# LAN8670_Watson.net
KiCad netlist of a schematic drawn in Altium Designer
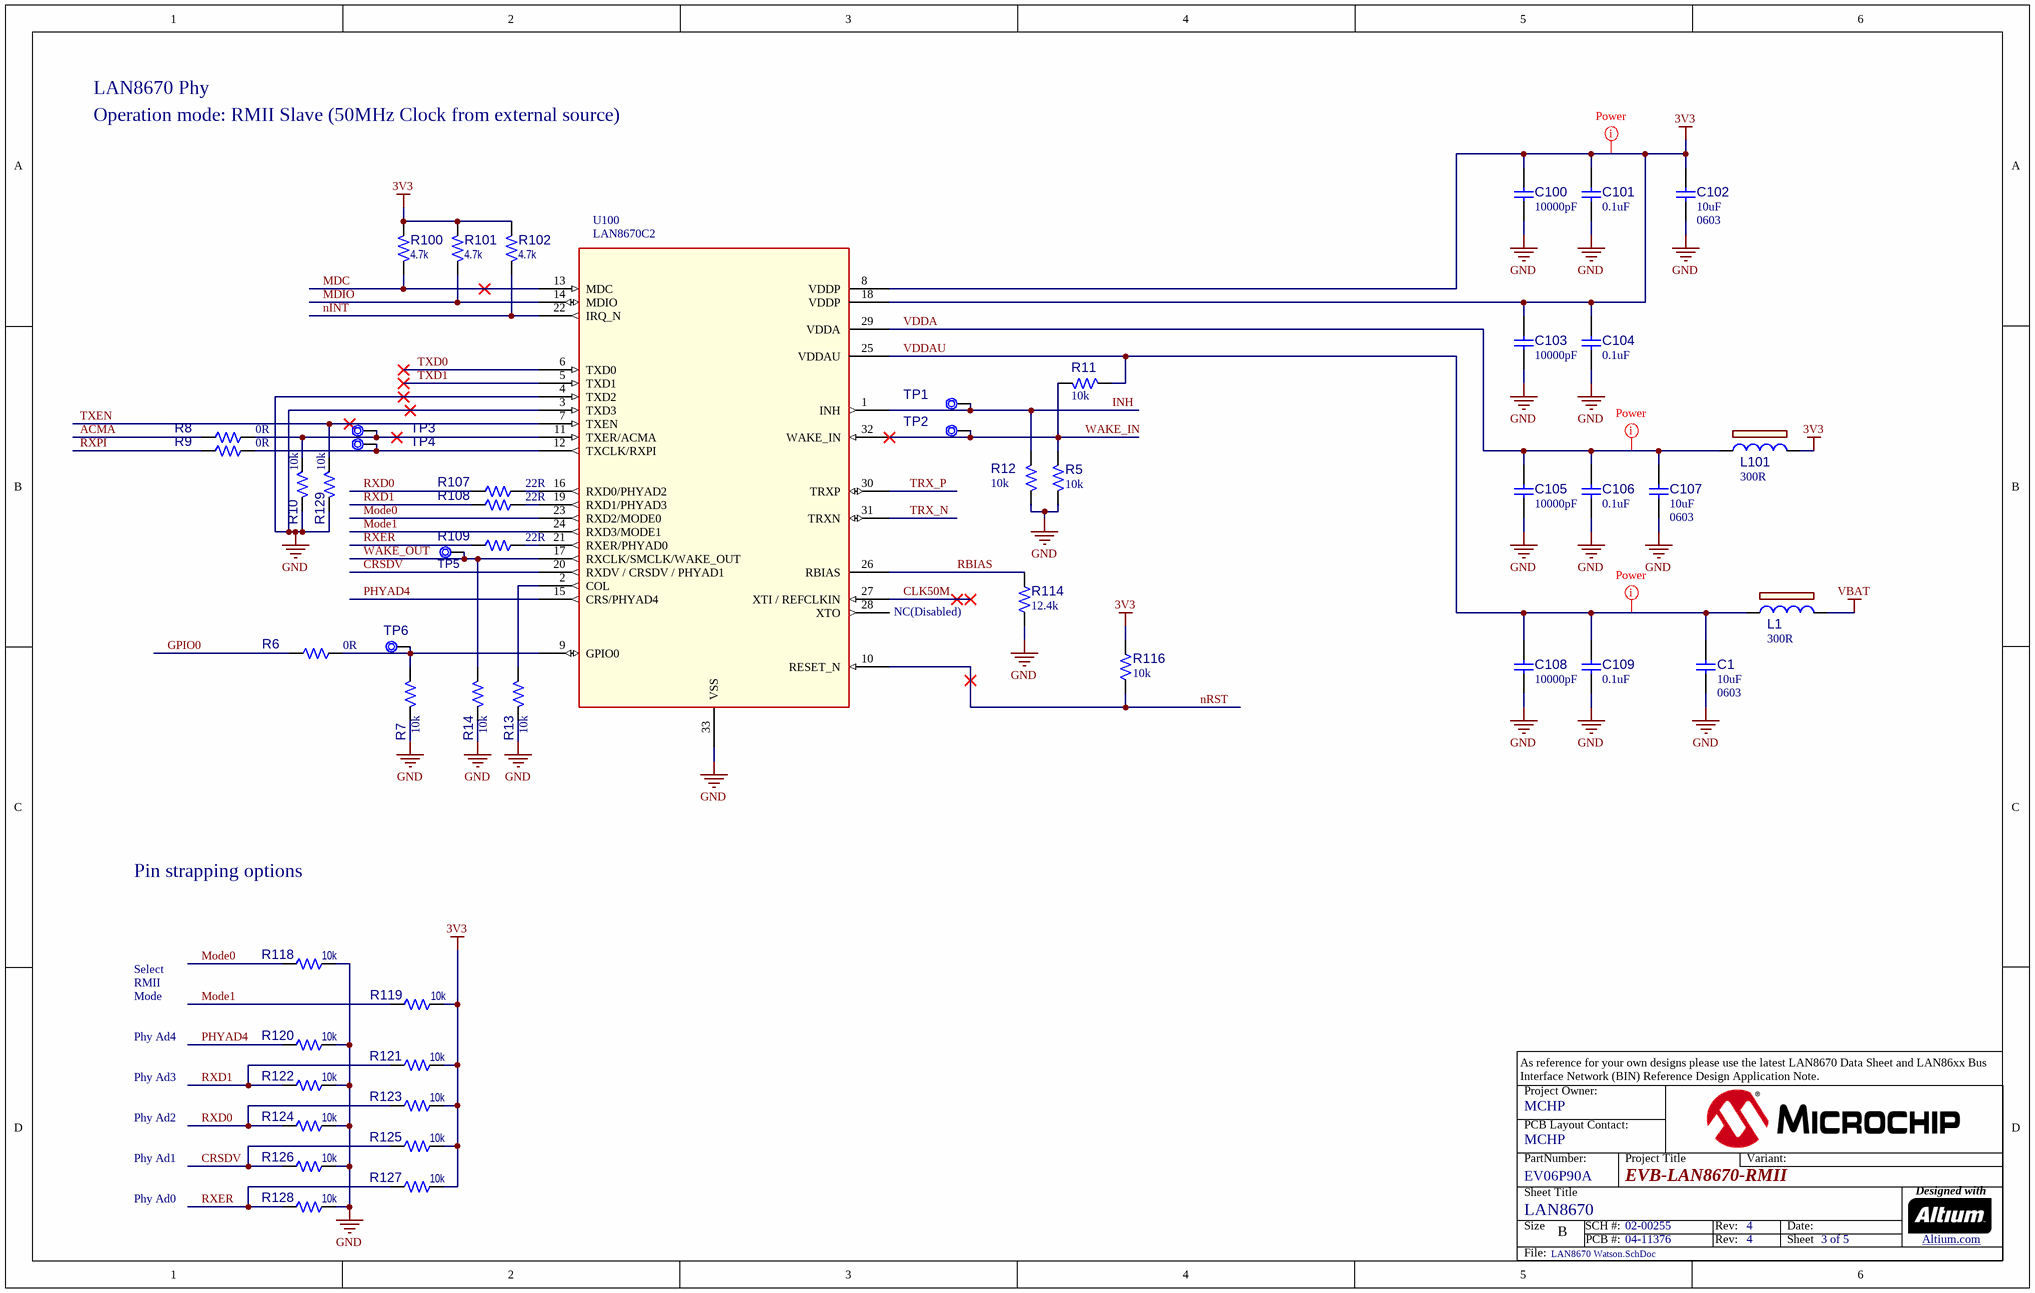
[diagram p0: LAN8670 Watson.SchDoc]

(export (version "E")
  (design (tool "Eeschema 10.0.6"))
  (components
    (comp (ref "C1")
      (value "10uF")
      (footprint "CAP_C_0603")
      (fields
        (field (name "VOLTAGE") "10V")
        (field (name "PACKAGE") "0603")
        (field (name "TOLERANCE") "20%")
        (field (name "Comment") "Capacitor NP")
      )
      (libsource (lib "") (part "Capacitor NP_1"))
    )
    (comp (ref "C100")
      (value "10000pF")
      (footprint "CAP_C_0402")
      (fields
        (field (name "VOLTAGE") "50V")
        (field (name "TOLERANCE") "10%")
        (field (name "Comment") "Capacitor NP")
        (field (name "OWNER") "Gabor Bihari")
      )
      (libsource (lib "MCHP-CDB-Offline") (part "Capacitor NP"))
    )
    (comp (ref "C101")
      (value "0.1uF")
      (footprint "CAP_C_0402")
      (description "Capacitor")
      (fields
        (field (name "VOLTAGE") "16V")
        (field (name "TOLERANCE") "10%")
        (field (name "OWNER") "Sompoch Loboonlert")
      )
      (libsource (lib "MCHP-CDB") (part "Capacitor NP"))
    )
    (comp (ref "C102")
      (value "10uF")
      (footprint "CAP_C_0603")
      (description "Capacitor")
      (fields (field (name "VOLTAGE") "10V") (field (name "PACKAGE") "0603") (field (name "TOLERANCE") "20%"))
      (libsource (lib "MCHP-CDB") (part "Capacitor NP"))
    )
    (comp (ref "C103")
      (value "10000pF")
      (footprint "CAP_C_0402")
      (fields
        (field (name "VOLTAGE") "50V")
        (field (name "TOLERANCE") "10%")
        (field (name "Comment") "Capacitor NP")
        (field (name "OWNER") "Gabor Bihari")
      )
      (libsource (lib "MCHP-CDB-Offline") (part "Capacitor NP"))
    )
    (comp (ref "C104")
      (value "0.1uF")
      (footprint "CAP_C_0402")
      (description "Capacitor")
      (fields
        (field (name "VOLTAGE") "16V")
        (field (name "TOLERANCE") "10%")
        (field (name "OWNER") "Sompoch Loboonlert")
      )
      (libsource (lib "MCHP-CDB") (part "Capacitor NP"))
    )
    (comp (ref "C105")
      (value "10000pF")
      (footprint "CAP_C_0402")
      (fields
        (field (name "VOLTAGE") "50V")
        (field (name "TOLERANCE") "10%")
        (field (name "Comment") "Capacitor NP")
        (field (name "OWNER") "Gabor Bihari")
      )
      (libsource (lib "MCHP-CDB-Offline") (part "Capacitor NP"))
    )
    (comp (ref "C106")
      (value "0.1uF")
      (footprint "CAP_C_0402")
      (description "Capacitor")
      (fields
        (field (name "VOLTAGE") "16V")
        (field (name "TOLERANCE") "10%")
        (field (name "OWNER") "Sompoch Loboonlert")
      )
      (libsource (lib "MCHP-CDB") (part "Capacitor NP"))
    )
    (comp (ref "C107")
      (value "10uF")
      (footprint "CAP_C_0603")
      (description "Capacitor")
      (fields (field (name "VOLTAGE") "10V") (field (name "PACKAGE") "0603") (field (name "TOLERANCE") "20%"))
      (libsource (lib "MCHP-CDB") (part "Capacitor NP"))
    )
    (comp (ref "C108")
      (value "10000pF")
      (footprint "CAP_C_0402")
      (fields
        (field (name "VOLTAGE") "50V")
        (field (name "TOLERANCE") "10%")
        (field (name "Comment") "Capacitor NP")
        (field (name "OWNER") "Gabor Bihari")
      )
      (libsource (lib "MCHP-CDB-Offline") (part "Capacitor NP"))
    )
    (comp (ref "C109")
      (value "0.1uF")
      (footprint "CAP_C_0402")
      (description "Capacitor")
      (fields
        (field (name "VOLTAGE") "16V")
        (field (name "TOLERANCE") "10%")
        (field (name "OWNER") "Sompoch Loboonlert")
      )
      (libsource (lib "MCHP-CDB") (part "Capacitor NP"))
    )
    (comp (ref "L1")
      (value "300R")
      (footprint "IND_C_0603")
      (fields (field (name "Comment") "Ferrite Bead") (field (name "OWNER") "Lori Graham"))
      (libsource (lib "MCHP-CDB") (part "Ferrite Bead"))
    )
    (comp (ref "L101")
      (value "300R")
      (footprint "IND_C_0603")
      (fields (field (name "Comment") "Ferrite Bead") (field (name "OWNER") "Lori Graham"))
      (libsource (lib "MCL-Offline") (part "Ferrite Bead"))
    )
    (comp (ref "R5")
      (value "10k")
      (footprint "RES_C_0402")
      (description "Resistor")
      (fields
        (field (name "VOLTAGE") "50V")
        (field (name "POWER") "1/10W")
        (field (name "OWNER") "Brent Lanphear")
      )
      (libsource (lib "") (part "Resistor_1"))
    )
    (comp (ref "R6")
      (value "0R")
      (footprint "RES_C_0402")
      (description "Resistor")
      (fields
        (field (name "TOLERANCE") "50mOhm")
        (field (name "POWER") "1/10W")
        (field (name "OWNER") "Dragos Danaila")
      )
      (libsource (lib "MCL-Offline") (part "Resistor"))
    )
    (comp (ref "R7")
      (value "10k")
      (footprint "RES_C_0402")
      (description "Resistor")
      (fields
        (field (name "TOLERANCE") "1%")
        (field (name "VOLTAGE") "50V")
        (field (name "OWNER") "Brent Lanphear")
      )
      (libsource (lib "MCHP-CDB") (part "Resistor"))
    )
    (comp (ref "R8")
      (value "0R")
      (footprint "RES_C_0402")
      (description "Resistor")
      (fields
        (field (name "TOLERANCE") "50mOhm")
        (field (name "POWER") "1/10W")
        (field (name "OWNER") "Dragos Danaila")
      )
      (libsource (lib "MCL-Offline") (part "Resistor"))
    )
    (comp (ref "R9")
      (value "0R")
      (footprint "RES_C_0402")
      (description "Resistor")
      (fields
        (field (name "TOLERANCE") "50mOhm")
        (field (name "POWER") "1/10W")
        (field (name "OWNER") "Dragos Danaila")
      )
      (libsource (lib "MCL-Offline") (part "Resistor"))
    )
    (comp (ref "R10")
      (value "10k")
      (footprint "RES_C_0402")
      (description "Resistor")
      (fields
        (field (name "TOLERANCE") "1%")
        (field (name "VOLTAGE") "50V")
        (field (name "OWNER") "Brent Lanphear")
      )
      (libsource (lib "MCHP-CDB") (part "Resistor"))
    )
    (comp (ref "R11")
      (value "10k")
      (footprint "RES_C_0402")
      (description "Resistor")
      (fields
        (field (name "TOLERANCE") "1%")
        (field (name "VOLTAGE") "50V")
        (field (name "OWNER") "Brent Lanphear")
      )
      (libsource (lib "MCHP-CDB") (part "Resistor"))
    )
    (comp (ref "R12")
      (value "10k")
      (footprint "RES_C_0402")
      (description "Resistor")
      (fields
        (field (name "TOLERANCE") "1%")
        (field (name "VOLTAGE") "50V")
        (field (name "OWNER") "Brent Lanphear")
      )
      (libsource (lib "MCHP-CDB") (part "Resistor"))
    )
    (comp (ref "R13")
      (value "10k")
      (footprint "RES_C_0402")
      (description "Resistor")
      (fields
        (field (name "TOLERANCE") "1%")
        (field (name "VOLTAGE") "50V")
        (field (name "OWNER") "Brent Lanphear")
      )
      (libsource (lib "MCHP-CDB") (part "Resistor"))
    )
    (comp (ref "R14")
      (value "10k")
      (footprint "RES_C_0402")
      (description "Resistor")
      (fields
        (field (name "TOLERANCE") "1%")
        (field (name "VOLTAGE") "50V")
        (field (name "OWNER") "Brent Lanphear")
      )
      (libsource (lib "MCHP-CDB") (part "Resistor"))
    )
    (comp (ref "R100")
      (value "4.7k")
      (footprint "RES_C_0402")
      (description "Resistor")
      (fields
        (field (name "VOLTAGE") "50V")
        (field (name "POWER") "1/10W")
        (field (name "OWNER") "Stephen Humberd")
      )
      (libsource (lib "MCHP-CDB") (part "Resistor"))
    )
    (comp (ref "R101")
      (value "4.7k")
      (footprint "RES_C_0402")
      (description "Resistor")
      (fields
        (field (name "VOLTAGE") "50V")
        (field (name "POWER") "1/10W")
        (field (name "OWNER") "Stephen Humberd")
      )
      (libsource (lib "MCHP-CDB") (part "Resistor"))
    )
    (comp (ref "R102")
      (value "4.7k")
      (footprint "RES_C_0402")
      (description "Resistor")
      (fields
        (field (name "VOLTAGE") "50V")
        (field (name "POWER") "1/10W")
        (field (name "OWNER") "Stephen Humberd")
      )
      (libsource (lib "MCHP-CDB") (part "Resistor"))
    )
    (comp (ref "R107")
      (value "22R")
      (footprint "RES_C_0402")
      (description "Resistor")
      (fields
        (field (name "TOLERANCE") "1%")
        (field (name "POWER") "1/10W")
        (field (name "OWNER") "Mike Ragsdale")
      )
      (libsource (lib "MCHP-CDB-Offline") (part "Resistor"))
    )
    (comp (ref "R108")
      (value "22R")
      (footprint "RES_C_0402")
      (description "Resistor")
      (fields
        (field (name "TOLERANCE") "1%")
        (field (name "POWER") "1/10W")
        (field (name "OWNER") "Mike Ragsdale")
      )
      (libsource (lib "MCHP-CDB-Offline") (part "Resistor"))
    )
    (comp (ref "R109")
      (value "22R")
      (footprint "RES_C_0402")
      (description "Resistor")
      (fields
        (field (name "TOLERANCE") "1%")
        (field (name "POWER") "1/10W")
        (field (name "OWNER") "Mike Ragsdale")
      )
      (libsource (lib "MCHP-CDB-Offline") (part "Resistor"))
    )
    (comp (ref "R114")
      (value "12.4k")
      (footprint "RES_C_0402")
      (description "Resistor")
      (fields
        (field (name "TOLERANCE") "±1%")
        (field (name "POWER") "1/10W")
        (field (name "OWNER") "Lori Graham")
      )
      (libsource (lib "MCL-Offline") (part "Resistor"))
    )
    (comp (ref "R116")
      (value "10k")
      (footprint "RES_C_0402")
      (description "Resistor")
      (fields
        (field (name "TOLERANCE") "1%")
        (field (name "VOLTAGE") "50V")
        (field (name "OWNER") "Brent Lanphear")
      )
      (libsource (lib "") (part "Resistor_1"))
    )
    (comp (ref "R118")
      (value "10k")
      (footprint "RES_C_0402")
      (description "Resistor")
      (fields
        (field (name "TOLERANCE") "1%")
        (field (name "VOLTAGE") "50V")
        (field (name "OWNER") "Brent Lanphear")
      )
      (libsource (lib "MCHP-CDB") (part "Resistor"))
    )
    (comp (ref "R119")
      (value "10k")
      (footprint "RES_C_0402")
      (description "Resistor")
      (fields
        (field (name "TOLERANCE") "1%")
        (field (name "VOLTAGE") "50V")
        (field (name "OWNER") "Brent Lanphear")
      )
      (libsource (lib "MCHP-CDB") (part "Resistor"))
    )
    (comp (ref "R120")
      (value "10k")
      (footprint "RES_C_0402")
      (description "Resistor")
      (fields
        (field (name "TOLERANCE") "1%")
        (field (name "VOLTAGE") "50V")
        (field (name "OWNER") "Brent Lanphear")
      )
      (libsource (lib "MCHP-CDB") (part "Resistor"))
    )
    (comp (ref "R121")
      (value "10k")
      (footprint "RES_C_0402")
      (description "Resistor")
      (fields
        (field (name "TOLERANCE") "1%")
        (field (name "VOLTAGE") "50V")
        (field (name "OWNER") "Brent Lanphear")
      )
      (libsource (lib "MCHP-CDB") (part "Resistor"))
    )
    (comp (ref "R122")
      (value "10k")
      (footprint "RES_C_0402")
      (description "Resistor")
      (fields
        (field (name "TOLERANCE") "1%")
        (field (name "VOLTAGE") "50V")
        (field (name "OWNER") "Brent Lanphear")
      )
      (libsource (lib "MCHP-CDB") (part "Resistor"))
    )
    (comp (ref "R123")
      (value "10k")
      (footprint "RES_C_0402")
      (description "Resistor")
      (fields
        (field (name "TOLERANCE") "1%")
        (field (name "VOLTAGE") "50V")
        (field (name "OWNER") "Brent Lanphear")
      )
      (libsource (lib "MCHP-CDB") (part "Resistor"))
    )
    (comp (ref "R124")
      (value "10k")
      (footprint "RES_C_0402")
      (description "Resistor")
      (fields
        (field (name "TOLERANCE") "1%")
        (field (name "VOLTAGE") "50V")
        (field (name "OWNER") "Brent Lanphear")
      )
      (libsource (lib "MCHP-CDB") (part "Resistor"))
    )
    (comp (ref "R125")
      (value "10k")
      (footprint "RES_C_0402")
      (description "Resistor")
      (fields
        (field (name "TOLERANCE") "1%")
        (field (name "VOLTAGE") "50V")
        (field (name "OWNER") "Brent Lanphear")
      )
      (libsource (lib "MCHP-CDB") (part "Resistor"))
    )
    (comp (ref "R126")
      (value "10k")
      (footprint "RES_C_0402")
      (description "Resistor")
      (fields
        (field (name "TOLERANCE") "1%")
        (field (name "VOLTAGE") "50V")
        (field (name "OWNER") "Brent Lanphear")
      )
      (libsource (lib "MCHP-CDB") (part "Resistor"))
    )
    (comp (ref "R127")
      (value "10k")
      (footprint "RES_C_0402")
      (description "Resistor")
      (fields
        (field (name "TOLERANCE") "1%")
        (field (name "VOLTAGE") "50V")
        (field (name "OWNER") "Brent Lanphear")
      )
      (libsource (lib "MCHP-CDB") (part "Resistor"))
    )
    (comp (ref "R128")
      (value "10k")
      (footprint "RES_C_0402")
      (description "Resistor")
      (fields
        (field (name "TOLERANCE") "1%")
        (field (name "VOLTAGE") "50V")
        (field (name "OWNER") "Brent Lanphear")
      )
      (libsource (lib "MCHP-CDB") (part "Resistor"))
    )
    (comp (ref "R129")
      (value "10k")
      (footprint "RES_C_0402")
      (description "Resistor")
      (fields
        (field (name "TOLERANCE") "1%")
        (field (name "VOLTAGE") "50V")
        (field (name "OWNER") "Brent Lanphear")
      )
      (libsource (lib "MCHP-CDB") (part "Resistor"))
    )
    (comp (ref "TP1")
      (value "Test Point No BOM")
      (footprint "TP_rd_0.5mm")
      (description "Test Point")
      (fields (field (name "OWNER") "JBU  (M21065)"))
      (libsource (lib "AIS-CDB-Offline") (part "Test Point No BOM"))
    )
    (comp (ref "TP2")
      (value "Test Point No BOM")
      (footprint "TP_rd_0.5mm")
      (description "Test Point")
      (fields (field (name "OWNER") "JBU  (M21065)"))
      (libsource (lib "AIS-CDB-Offline") (part "Test Point No BOM"))
    )
    (comp (ref "TP3")
      (value "Test Point No BOM")
      (footprint "TP_rd_0.5mm")
      (description "Test Point")
      (fields (field (name "OWNER") "JBU  (M21065)"))
      (libsource (lib "AIS-CDB-Offline") (part "Test Point No BOM"))
    )
    (comp (ref "TP4")
      (value "Test Point No BOM")
      (footprint "TP_rd_0.5mm")
      (description "Test Point")
      (fields (field (name "OWNER") "JBU  (M21065)"))
      (libsource (lib "AIS-CDB-Offline") (part "Test Point No BOM"))
    )
    (comp (ref "TP5")
      (value "Test Point No BOM")
      (footprint "TP_rd_0.5mm")
      (description "Test Point")
      (fields (field (name "OWNER") "JBU  (M21065)"))
      (libsource (lib "AIS-CDB-Offline") (part "Test Point No BOM"))
    )
    (comp (ref "TP6")
      (value "Test Point No BOM")
      (footprint "TP_rd_0.5mm")
      (description "Test Point")
      (fields (field (name "OWNER") "JBU  (M21065)"))
      (libsource (lib "AIS-CDB-Offline") (part "Test Point No BOM"))
    )
    (comp (ref "U100")
      (value "LAN8670C2")
      (footprint "VQFN-32_5x5_EP3.3x3.3")
      (fields (field (name "Comment") "LAN8670C VQFN-32") (field (name "OWNER") "Lori Cantrell"))
      (libsource (lib "MCL-Offline") (part "LAN8670C VQFN-32"))
    )
  )
  (nets
    (net (code "1") (name "/ACMA") (class "Default")
      (node (ref "R8") (pin "1") (pinfunction "1_1") (pintype "passive"))
    )
    (net (code "2") (name "/CLK50M") (class "Default")
      (node (ref "U100") (pin "27") (pinfunction "XTI_/_REFCLKIN_27") (pintype "input+no_connect"))
    )
    (net (code "3") (name "/CRSDV") (class "Default")
      (node (ref "R125") (pin "1") (pinfunction "1_1") (pintype "passive"))
      (node (ref "R126") (pin "1") (pinfunction "1_1") (pintype "passive"))
      (node (ref "U100") (pin "20") (pinfunction "RXDV_/_CRSDV_/_PHYAD1_20") (pintype "output"))
    )
    (net (code "4") (name "/GPIO0") (class "Default")
      (node (ref "R6") (pin "1") (pinfunction "1_1") (pintype "passive"))
    )
    (net (code "5") (name "/INH") (class "Default")
      (node (ref "R12") (pin "2") (pinfunction "2_2") (pintype "passive"))
      (node (ref "TP1") (pin "1") (pinfunction "1_1") (pintype "passive"))
      (node (ref "U100") (pin "1") (pinfunction "INH_1") (pintype "output"))
    )
    (net (code "6") (name "/MDC") (class "Default")
      (node (ref "R100") (pin "1") (pinfunction "1_1") (pintype "passive"))
      (node (ref "U100") (pin "13") (pinfunction "MDC_13") (pintype "input"))
    )
    (net (code "7") (name "/MDIO") (class "Default")
      (node (ref "R101") (pin "1") (pinfunction "1_1") (pintype "passive"))
      (node (ref "U100") (pin "14") (pinfunction "MDIO_14") (pintype "bidirectional"))
    )
    (net (code "8") (name "/Mode0") (class "Default")
      (node (ref "R118") (pin "1") (pinfunction "1_1") (pintype "passive"))
      (node (ref "U100") (pin "23") (pinfunction "RXD2/MODE0_23") (pintype "output"))
    )
    (net (code "9") (name "/Mode1") (class "Default")
      (node (ref "R119") (pin "1") (pinfunction "1_1") (pintype "passive"))
      (node (ref "U100") (pin "24") (pinfunction "RXD3/MODE1_24") (pintype "output"))
    )
    (net (code "10") (name "/PHYAD4") (class "Default")
      (node (ref "R120") (pin "1") (pinfunction "1_1") (pintype "passive"))
      (node (ref "U100") (pin "15") (pinfunction "CRS/PHYAD4_15") (pintype "output"))
    )
    (net (code "11") (name "/RBIAS") (class "Default")
      (node (ref "R114") (pin "2") (pinfunction "2_2") (pintype "passive"))
      (node (ref "U100") (pin "26") (pinfunction "RBIAS_26") (pintype "passive"))
    )
    (net (code "12") (name "/RXD0") (class "Default")
      (node (ref "R107") (pin "1") (pinfunction "1_1") (pintype "passive"))
      (node (ref "R123") (pin "1") (pinfunction "1_1") (pintype "passive"))
      (node (ref "R124") (pin "1") (pinfunction "1_1") (pintype "passive"))
    )
    (net (code "13") (name "/RXD1") (class "Default")
      (node (ref "R108") (pin "1") (pinfunction "1_1") (pintype "passive"))
      (node (ref "R121") (pin "1") (pinfunction "1_1") (pintype "passive"))
      (node (ref "R122") (pin "1") (pinfunction "1_1") (pintype "passive"))
    )
    (net (code "14") (name "/RXER") (class "Default")
      (node (ref "R109") (pin "1") (pinfunction "1_1") (pintype "passive"))
      (node (ref "R127") (pin "1") (pinfunction "1_1") (pintype "passive"))
      (node (ref "R128") (pin "1") (pinfunction "1_1") (pintype "passive"))
    )
    (net (code "15") (name "/RXPI") (class "Default")
      (node (ref "R9") (pin "1") (pinfunction "1_1") (pintype "passive"))
    )
    (net (code "16") (name "/TRX_N") (class "Default")
      (node (ref "U100") (pin "31") (pinfunction "TRXN_31") (pintype "bidirectional"))
    )
    (net (code "17") (name "/TRX_P") (class "Default")
      (node (ref "U100") (pin "30") (pinfunction "TRXP_30") (pintype "bidirectional"))
    )
    (net (code "18") (name "/TXD0") (class "Default")
      (node (ref "U100") (pin "6") (pinfunction "TXD0_6") (pintype "input+no_connect"))
    )
    (net (code "19") (name "/TXD1") (class "Default")
      (node (ref "U100") (pin "5") (pinfunction "TXD1_5") (pintype "input+no_connect"))
    )
    (net (code "20") (name "/TXEN") (class "Default")
      (node (ref "R129") (pin "2") (pinfunction "2_2") (pintype "passive"))
      (node (ref "U100") (pin "7") (pinfunction "TXEN_7") (pintype "input"))
    )
    (net (code "21") (name "/VDDA") (class "Default")
      (node (ref "C105") (pin "2") (pinfunction "2_2") (pintype "passive"))
      (node (ref "C106") (pin "2") (pinfunction "2_2") (pintype "passive"))
      (node (ref "C107") (pin "2") (pinfunction "2_2") (pintype "passive"))
      (node (ref "L101") (pin "1") (pinfunction "1_1") (pintype "passive"))
      (node (ref "U100") (pin "29") (pinfunction "VDDA_29") (pintype "power_in"))
    )
    (net (code "22") (name "/VDDAU") (class "Default")
      (node (ref "C1") (pin "2") (pinfunction "2_2") (pintype "passive"))
      (node (ref "C108") (pin "2") (pinfunction "2_2") (pintype "passive"))
      (node (ref "C109") (pin "2") (pinfunction "2_2") (pintype "passive"))
      (node (ref "L1") (pin "1") (pinfunction "1_1") (pintype "passive"))
      (node (ref "R11") (pin "1") (pinfunction "1_1") (pintype "passive"))
      (node (ref "U100") (pin "25") (pinfunction "VDDAU_25") (pintype "power_in"))
    )
    (net (code "23") (name "/WAKE_IN") (class "Default")
      (node (ref "R11") (pin "2") (pinfunction "2_2") (pintype "passive"))
      (node (ref "R5") (pin "2") (pinfunction "2_2") (pintype "passive"))
      (node (ref "TP2") (pin "1") (pinfunction "1_1") (pintype "passive"))
      (node (ref "U100") (pin "32") (pinfunction "WAKE_IN_32") (pintype "input"))
    )
    (net (code "24") (name "/WAKE_OUT") (class "Default")
      (node (ref "R14") (pin "2") (pinfunction "2_2") (pintype "passive"))
      (node (ref "TP5") (pin "1") (pinfunction "1_1") (pintype "passive"))
      (node (ref "U100") (pin "17") (pinfunction "RXCLK/SMCLK/WAKE_OUT_17") (pintype "output"))
    )
    (net (code "25") (name "/nINT") (class "Default")
      (node (ref "R102") (pin "1") (pinfunction "1_1") (pintype "passive"))
      (node (ref "U100") (pin "22") (pinfunction "IRQ_N_22") (pintype "output"))
    )
    (net (code "26") (name "/nRST") (class "Default")
      (node (ref "R116") (pin "1") (pinfunction "1_1") (pintype "passive"))
      (node (ref "U100") (pin "10") (pinfunction "RESET_N_10") (pintype "input"))
    )
    (net (code "27") (name "3V3") (class "Default")
      (node (ref "C100") (pin "2") (pinfunction "2_2") (pintype "passive"))
      (node (ref "C101") (pin "2") (pinfunction "2_2") (pintype "passive"))
      (node (ref "C102") (pin "2") (pinfunction "2_2") (pintype "passive"))
      (node (ref "C103") (pin "2") (pinfunction "2_2") (pintype "passive"))
      (node (ref "C104") (pin "2") (pinfunction "2_2") (pintype "passive"))
      (node (ref "L101") (pin "2") (pinfunction "2_2") (pintype "passive"))
      (node (ref "R100") (pin "2") (pinfunction "2_2") (pintype "passive"))
      (node (ref "R101") (pin "2") (pinfunction "2_2") (pintype "passive"))
      (node (ref "R102") (pin "2") (pinfunction "2_2") (pintype "passive"))
      (node (ref "R116") (pin "2") (pinfunction "2_2") (pintype "passive"))
      (node (ref "R119") (pin "2") (pinfunction "2_2") (pintype "passive"))
      (node (ref "R121") (pin "2") (pinfunction "2_2") (pintype "passive"))
      (node (ref "R123") (pin "2") (pinfunction "2_2") (pintype "passive"))
      (node (ref "R125") (pin "2") (pinfunction "2_2") (pintype "passive"))
      (node (ref "R127") (pin "2") (pinfunction "2_2") (pintype "passive"))
      (node (ref "U100") (pin "18") (pinfunction "VDDP_18") (pintype "power_in"))
      (node (ref "U100") (pin "8") (pinfunction "VDDP_8") (pintype "power_in"))
    )
    (net (code "28") (name "GND") (class "Default")
      (node (ref "C1") (pin "1") (pinfunction "1_1") (pintype "passive"))
      (node (ref "C100") (pin "1") (pinfunction "1_1") (pintype "passive"))
      (node (ref "C101") (pin "1") (pinfunction "1_1") (pintype "passive"))
      (node (ref "C102") (pin "1") (pinfunction "1_1") (pintype "passive"))
      (node (ref "C103") (pin "1") (pinfunction "1_1") (pintype "passive"))
      (node (ref "C104") (pin "1") (pinfunction "1_1") (pintype "passive"))
      (node (ref "C105") (pin "1") (pinfunction "1_1") (pintype "passive"))
      (node (ref "C106") (pin "1") (pinfunction "1_1") (pintype "passive"))
      (node (ref "C107") (pin "1") (pinfunction "1_1") (pintype "passive"))
      (node (ref "C108") (pin "1") (pinfunction "1_1") (pintype "passive"))
      (node (ref "C109") (pin "1") (pinfunction "1_1") (pintype "passive"))
      (node (ref "R10") (pin "1") (pinfunction "1_1") (pintype "passive"))
      (node (ref "R114") (pin "1") (pinfunction "1_1") (pintype "passive"))
      (node (ref "R118") (pin "2") (pinfunction "2_2") (pintype "passive"))
      (node (ref "R12") (pin "1") (pinfunction "1_1") (pintype "passive"))
      (node (ref "R120") (pin "2") (pinfunction "2_2") (pintype "passive"))
      (node (ref "R122") (pin "2") (pinfunction "2_2") (pintype "passive"))
      (node (ref "R124") (pin "2") (pinfunction "2_2") (pintype "passive"))
      (node (ref "R126") (pin "2") (pinfunction "2_2") (pintype "passive"))
      (node (ref "R128") (pin "2") (pinfunction "2_2") (pintype "passive"))
      (node (ref "R129") (pin "1") (pinfunction "1_1") (pintype "passive"))
      (node (ref "R13") (pin "1") (pinfunction "1_1") (pintype "passive"))
      (node (ref "R14") (pin "1") (pinfunction "1_1") (pintype "passive"))
      (node (ref "R5") (pin "1") (pinfunction "1_1") (pintype "passive"))
      (node (ref "R7") (pin "1") (pinfunction "1_1") (pintype "passive"))
      (node (ref "U100") (pin "3") (pinfunction "TXD3_3") (pintype "input"))
      (node (ref "U100") (pin "33") (pinfunction "VSS_33") (pintype "power_in"))
      (node (ref "U100") (pin "4") (pinfunction "TXD2_4") (pintype "input"))
    )
    (net (code "29") (name "Net-(U100-COL)") (class "Default")
      (node (ref "R13") (pin "2") (pinfunction "2_2") (pintype "passive"))
      (node (ref "U100") (pin "2") (pinfunction "COL_2") (pintype "output"))
    )
    (net (code "30") (name "Net-(U100-GPIO0)") (class "Default")
      (node (ref "R6") (pin "2") (pinfunction "2_2") (pintype "passive"))
      (node (ref "R7") (pin "2") (pinfunction "2_2") (pintype "passive"))
      (node (ref "TP6") (pin "1") (pinfunction "1_1") (pintype "passive"))
      (node (ref "U100") (pin "9") (pinfunction "GPIO0_9") (pintype "bidirectional"))
    )
    (net (code "31") (name "Net-(U100-RXD0{slash}PHYAD2)") (class "Default")
      (node (ref "R107") (pin "2") (pinfunction "2_2") (pintype "passive"))
      (node (ref "U100") (pin "16") (pinfunction "RXD0/PHYAD2_16") (pintype "output"))
    )
    (net (code "32") (name "Net-(U100-RXD1{slash}PHYAD3)") (class "Default")
      (node (ref "R108") (pin "2") (pinfunction "2_2") (pintype "passive"))
      (node (ref "U100") (pin "19") (pinfunction "RXD1/PHYAD3_19") (pintype "output"))
    )
    (net (code "33") (name "Net-(U100-RXER{slash}PHYAD0)") (class "Default")
      (node (ref "R109") (pin "2") (pinfunction "2_2") (pintype "passive"))
      (node (ref "U100") (pin "21") (pinfunction "RXER/PHYAD0_21") (pintype "output"))
    )
    (net (code "34") (name "Net-(U100-TXCLK{slash}RXPI)") (class "Default")
      (node (ref "R9") (pin "2") (pinfunction "2_2") (pintype "passive"))
      (node (ref "TP4") (pin "1") (pinfunction "1_1") (pintype "passive"))
      (node (ref "U100") (pin "12") (pinfunction "TXCLK/RXPI_12") (pintype "output"))
    )
    (net (code "35") (name "Net-(U100-TXER{slash}ACMA)") (class "Default")
      (node (ref "R10") (pin "2") (pinfunction "2_2") (pintype "passive"))
      (node (ref "R8") (pin "2") (pinfunction "2_2") (pintype "passive"))
      (node (ref "TP3") (pin "1") (pinfunction "1_1") (pintype "passive"))
      (node (ref "U100") (pin "11") (pinfunction "TXER/ACMA_11") (pintype "input"))
    )
    (net (code "36") (name "VBAT") (class "Default")
      (node (ref "L1") (pin "2") (pinfunction "2_2") (pintype "passive"))
    )
    (net (code "37") (name "unconnected-(U100-XTO-Pad28)") (class "Default")
      (node (ref "U100") (pin "28") (pinfunction "XTO_28") (pintype "output"))
    )
  )
)
